# AtmelZLLBoard.net
KiCad netlist of a schematic drawn in EAGLE
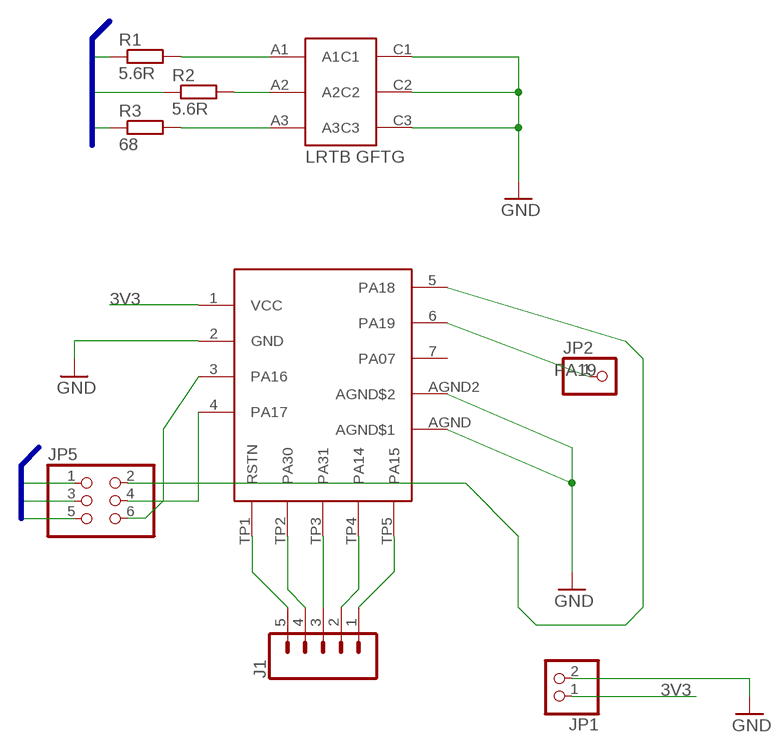
[diagram p0: schematic, sheet 1]

(export (version "E")
  (design (tool "Eeschema 10.0.6"))
  (components
    (comp (ref "J1")
      (value "CONN_05LOCK")
      (footprint "eagle-import:1X05_LOCK")
      (libsource (lib "eagle-import") (part "CONN_05LOCK"))
    )
    (comp (ref "JP1")
      (value "PINHD-1X2")
      (footprint "eagle-import:1X02")
      (libsource (lib "eagle-import") (part "PINHD-1X2"))
    )
    (comp (ref "JP2")
      (value "PINHD-1X1")
      (footprint "eagle-import:1X01")
      (libsource (lib "eagle-import") (part "PINHD-1X1"))
    )
    (comp (ref "JP5")
      (value "PINHD-2X3")
      (footprint "eagle-import:2X03")
      (libsource (lib "eagle-import") (part "PINHD-2X3"))
    )
    (comp (ref "R1")
      (value "5.6R")
      (footprint "eagle-import:0204_5")
      (libsource (lib "eagle-import") (part "R-EU_0204/5"))
    )
    (comp (ref "R2")
      (value "5.6R")
      (footprint "eagle-import:0204_5")
      (libsource (lib "eagle-import") (part "R-EU_0204/5"))
    )
    (comp (ref "R3")
      (value "68")
      (footprint "eagle-import:0204_5")
      (libsource (lib "eagle-import") (part "R-EU_0204/5"))
    )
    (comp (ref "U$1")
      (value "ATSAMR21B18-MZ210PA-DEV")
      (footprint "eagle-import:ATSAMR21B18-MZ210PA-DEV")
      (libsource (lib "eagle-import") (part "ATSAMR21B18-MZ210PA-DEV"))
    )
    (comp (ref "U$2")
      (value "LRTB_GFTG")
      (footprint "eagle-import:LRTB_GFTG")
      (libsource (lib "eagle-import") (part "LRTB_GFTG"))
    )
  )
  (nets
    (net (code "1") (name "/3V3") (class "Default")
      (node (ref "JP1") (pin "1") (pinfunction "1_1") (pintype "passive"))
      (node (ref "U$1") (pin "1") (pinfunction "VCC_1") (pintype "bidirectional"))
    )
    (net (code "2") (name "/B") (class "Default")
      (node (ref "JP5") (pin "1") (pinfunction "1_1") (pintype "passive"))
      (node (ref "R1") (pin "1") (pinfunction "1_1") (pintype "passive"))
    )
    (net (code "3") (name "/G") (class "Default")
      (node (ref "JP5") (pin "3") (pinfunction "3_3") (pintype "passive"))
      (node (ref "R2") (pin "1") (pinfunction "1_1") (pintype "passive"))
    )
    (net (code "4") (name "/PA19") (class "Default")
      (node (ref "JP2") (pin "1") (pinfunction "1_1") (pintype "passive"))
      (node (ref "U$1") (pin "6") (pinfunction "PA19_6") (pintype "bidirectional"))
    )
    (net (code "5") (name "/R") (class "Default")
      (node (ref "JP5") (pin "5") (pinfunction "5_5") (pintype "passive"))
      (node (ref "R3") (pin "1") (pinfunction "1_1") (pintype "passive"))
    )
    (net (code "6") (name "GND") (class "Default")
      (node (ref "JP1") (pin "2") (pinfunction "2_2") (pintype "passive"))
      (node (ref "U$1") (pin "2") (pinfunction "GND_2") (pintype "bidirectional"))
      (node (ref "U$1") (pin "AGND") (pinfunction "AGND$1_AGND") (pintype "bidirectional"))
      (node (ref "U$1") (pin "AGND2") (pinfunction "AGND$2_AGND2") (pintype "bidirectional"))
      (node (ref "U$2") (pin "C1") (pinfunction "C1_C1") (pintype "bidirectional"))
      (node (ref "U$2") (pin "C2") (pinfunction "C2_C2") (pintype "bidirectional"))
      (node (ref "U$2") (pin "C3") (pinfunction "C3_C3") (pintype "bidirectional"))
    )
    (net (code "7") (name "Net-(R1-Pad2)") (class "Default")
      (node (ref "R1") (pin "2") (pinfunction "2_2") (pintype "passive"))
      (node (ref "U$2") (pin "A1") (pinfunction "A1_A1") (pintype "bidirectional"))
    )
    (net (code "8") (name "Net-(R2-Pad2)") (class "Default")
      (node (ref "R2") (pin "2") (pinfunction "2_2") (pintype "passive"))
      (node (ref "U$2") (pin "A2") (pinfunction "A2_A2") (pintype "bidirectional"))
    )
    (net (code "9") (name "Net-(R3-Pad2)") (class "Default")
      (node (ref "R3") (pin "2") (pinfunction "2_2") (pintype "passive"))
      (node (ref "U$2") (pin "A3") (pinfunction "A3_A3") (pintype "bidirectional"))
    )
    (net (code "10") (name "Net-(U$1-PA14)") (class "Default")
      (node (ref "J1") (pin "2") (pinfunction "2_2") (pintype "passive"))
      (node (ref "U$1") (pin "TP4") (pinfunction "PA14_TP4") (pintype "bidirectional"))
    )
    (net (code "11") (name "Net-(U$1-PA15)") (class "Default")
      (node (ref "J1") (pin "1") (pinfunction "1_1") (pintype "passive"))
      (node (ref "U$1") (pin "TP5") (pinfunction "PA15_TP5") (pintype "bidirectional"))
    )
    (net (code "12") (name "Net-(U$1-PA16)") (class "Default")
      (node (ref "JP5") (pin "6") (pinfunction "6_6") (pintype "passive"))
      (node (ref "U$1") (pin "3") (pinfunction "PA16_3") (pintype "bidirectional"))
    )
    (net (code "13") (name "Net-(U$1-PA17)") (class "Default")
      (node (ref "JP5") (pin "4") (pinfunction "4_4") (pintype "passive"))
      (node (ref "U$1") (pin "4") (pinfunction "PA17_4") (pintype "bidirectional"))
    )
    (net (code "14") (name "Net-(U$1-PA18)") (class "Default")
      (node (ref "JP5") (pin "2") (pinfunction "2_2") (pintype "passive"))
      (node (ref "U$1") (pin "5") (pinfunction "PA18_5") (pintype "bidirectional"))
    )
    (net (code "15") (name "Net-(U$1-PA30)") (class "Default")
      (node (ref "J1") (pin "4") (pinfunction "4_4") (pintype "passive"))
      (node (ref "U$1") (pin "TP2") (pinfunction "PA30_TP2") (pintype "bidirectional"))
    )
    (net (code "16") (name "Net-(U$1-PA31)") (class "Default")
      (node (ref "J1") (pin "3") (pinfunction "3_3") (pintype "passive"))
      (node (ref "U$1") (pin "TP3") (pinfunction "PA31_TP3") (pintype "bidirectional"))
    )
    (net (code "17") (name "Net-(U$1-RSTN)") (class "Default")
      (node (ref "J1") (pin "5") (pinfunction "5_5") (pintype "passive"))
      (node (ref "U$1") (pin "TP1") (pinfunction "RSTN_TP1") (pintype "bidirectional"))
    )
    (net (code "18") (name "unconnected-(U$1-PA07-Pad7)") (class "Default")
      (node (ref "U$1") (pin "7") (pinfunction "PA07_7") (pintype "bidirectional"))
    )
  )
)
